# FLS_Clock_A_Distribution.net
KiCad netlist of a schematic drawn in Altium Designer
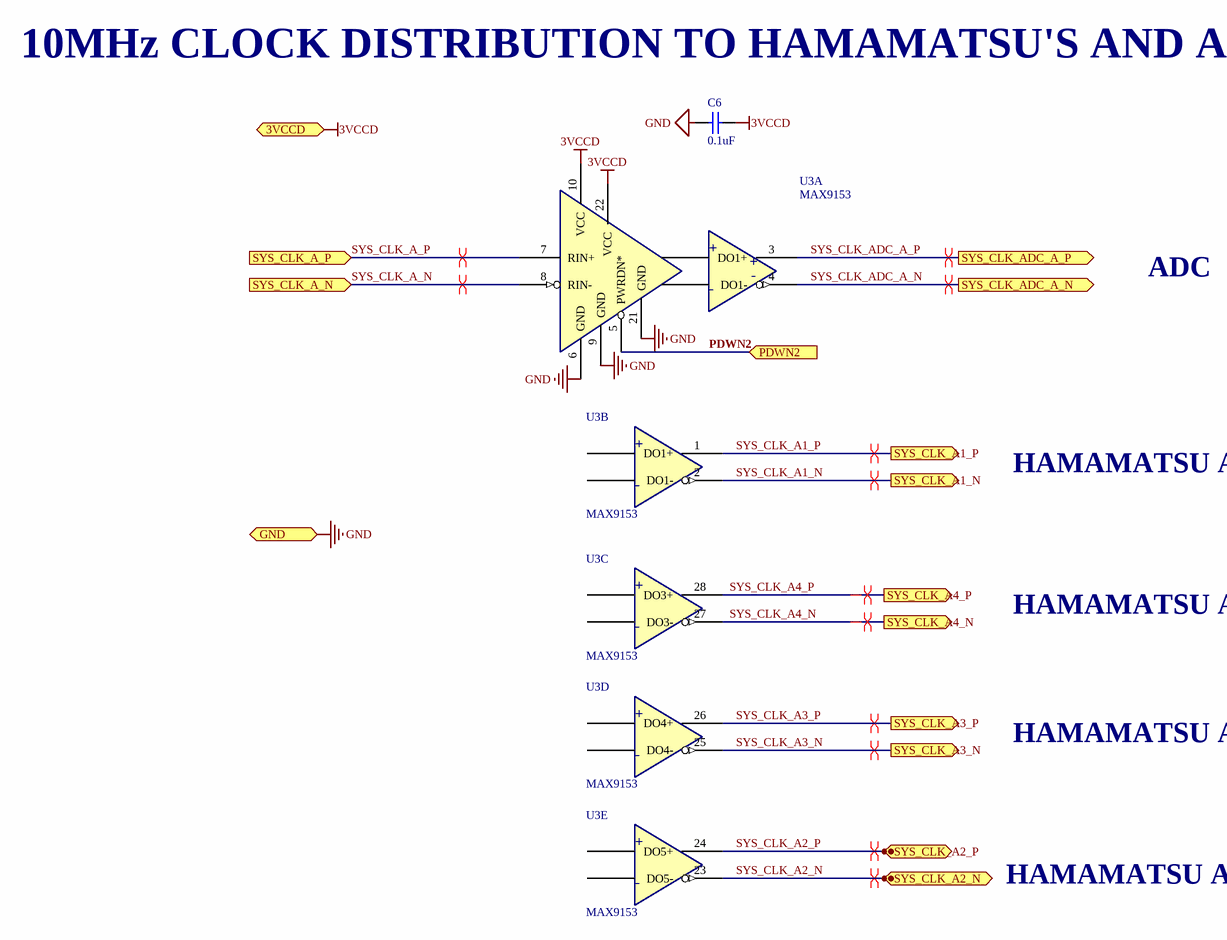
[diagram p0: FLS Clock_A Distribution.SchDoc]

(export (version "E")
  (design (tool "Eeschema 10.0.6"))
  (components
    (comp (ref "C6")
      (value "0.1uF")
      (footprint "0805 slim")
      (description "Capacitor")
      (fields (field (name "PUBLISHER") "Altium Limited"))
      (libsource (lib "FLS ADC_A") (part "Cap"))
    )
    (comp (ref "U3")
      (value "MAX9153")
      (footprint "MAX9153EUI")
      (libsource (lib "FLS ADC_A") (part "MAX9153"))
    )
  )
  (nets
    (net (code "1") (name "/PDWN2") (class "Default")
      (node (ref "U3") (pin "5") (pinfunction "PWRDN*_5") (pintype "power_in"))
    )
    (net (code "2") (name "/SYS_CLK_A1_N") (class "Default")
      (node (ref "U3") (pin "2") (pinfunction "DO1-_2") (pintype "output"))
    )
    (net (code "3") (name "/SYS_CLK_A1_P") (class "Default")
      (node (ref "U3") (pin "1") (pinfunction "DO1+_1") (pintype "passive"))
    )
    (net (code "4") (name "/SYS_CLK_A2_N") (class "Default")
      (node (ref "U3") (pin "23") (pinfunction "DO5-_23") (pintype "output"))
    )
    (net (code "5") (name "/SYS_CLK_A2_P") (class "Default")
      (node (ref "U3") (pin "24") (pinfunction "DO5+_24") (pintype "passive"))
    )
    (net (code "6") (name "/SYS_CLK_A3_N") (class "Default")
      (node (ref "U3") (pin "25") (pinfunction "DO4-_25") (pintype "output"))
    )
    (net (code "7") (name "/SYS_CLK_A3_P") (class "Default")
      (node (ref "U3") (pin "26") (pinfunction "DO4+_26") (pintype "passive"))
    )
    (net (code "8") (name "/SYS_CLK_A4_N") (class "Default")
      (node (ref "U3") (pin "27") (pinfunction "DO3-_27") (pintype "output"))
    )
    (net (code "9") (name "/SYS_CLK_A4_P") (class "Default")
      (node (ref "U3") (pin "28") (pinfunction "DO3+_28") (pintype "passive"))
    )
    (net (code "10") (name "/SYS_CLK_ADC_A_N") (class "Default")
      (node (ref "U3") (pin "4") (pinfunction "DO1-_4") (pintype "output"))
    )
    (net (code "11") (name "/SYS_CLK_ADC_A_P") (class "Default")
      (node (ref "U3") (pin "3") (pinfunction "DO1+_3") (pintype "passive"))
    )
    (net (code "12") (name "/SYS_CLK_A_N") (class "Default")
      (node (ref "U3") (pin "8") (pinfunction "RIN-_8") (pintype "input"))
    )
    (net (code "13") (name "/SYS_CLK_A_P") (class "Default")
      (node (ref "U3") (pin "7") (pinfunction "RIN+_7") (pintype "passive"))
    )
    (net (code "14") (name "3VCCD") (class "Default")
      (node (ref "C6") (pin "2") (pinfunction "2_2") (pintype "passive"))
      (node (ref "U3") (pin "10") (pinfunction "VCC_10") (pintype "power_in"))
      (node (ref "U3") (pin "22") (pinfunction "VCC_22") (pintype "power_in"))
    )
    (net (code "15") (name "GND") (class "Default")
      (node (ref "C6") (pin "1") (pinfunction "1_1") (pintype "passive"))
      (node (ref "U3") (pin "21") (pinfunction "GND_21") (pintype "power_in"))
      (node (ref "U3") (pin "6") (pinfunction "GND_6") (pintype "power_in"))
      (node (ref "U3") (pin "9") (pinfunction "GND_9") (pintype "power_in"))
    )
  )
)
